# FPGA_Bank_IO.net
KiCad netlist of a schematic drawn in Altium Designer
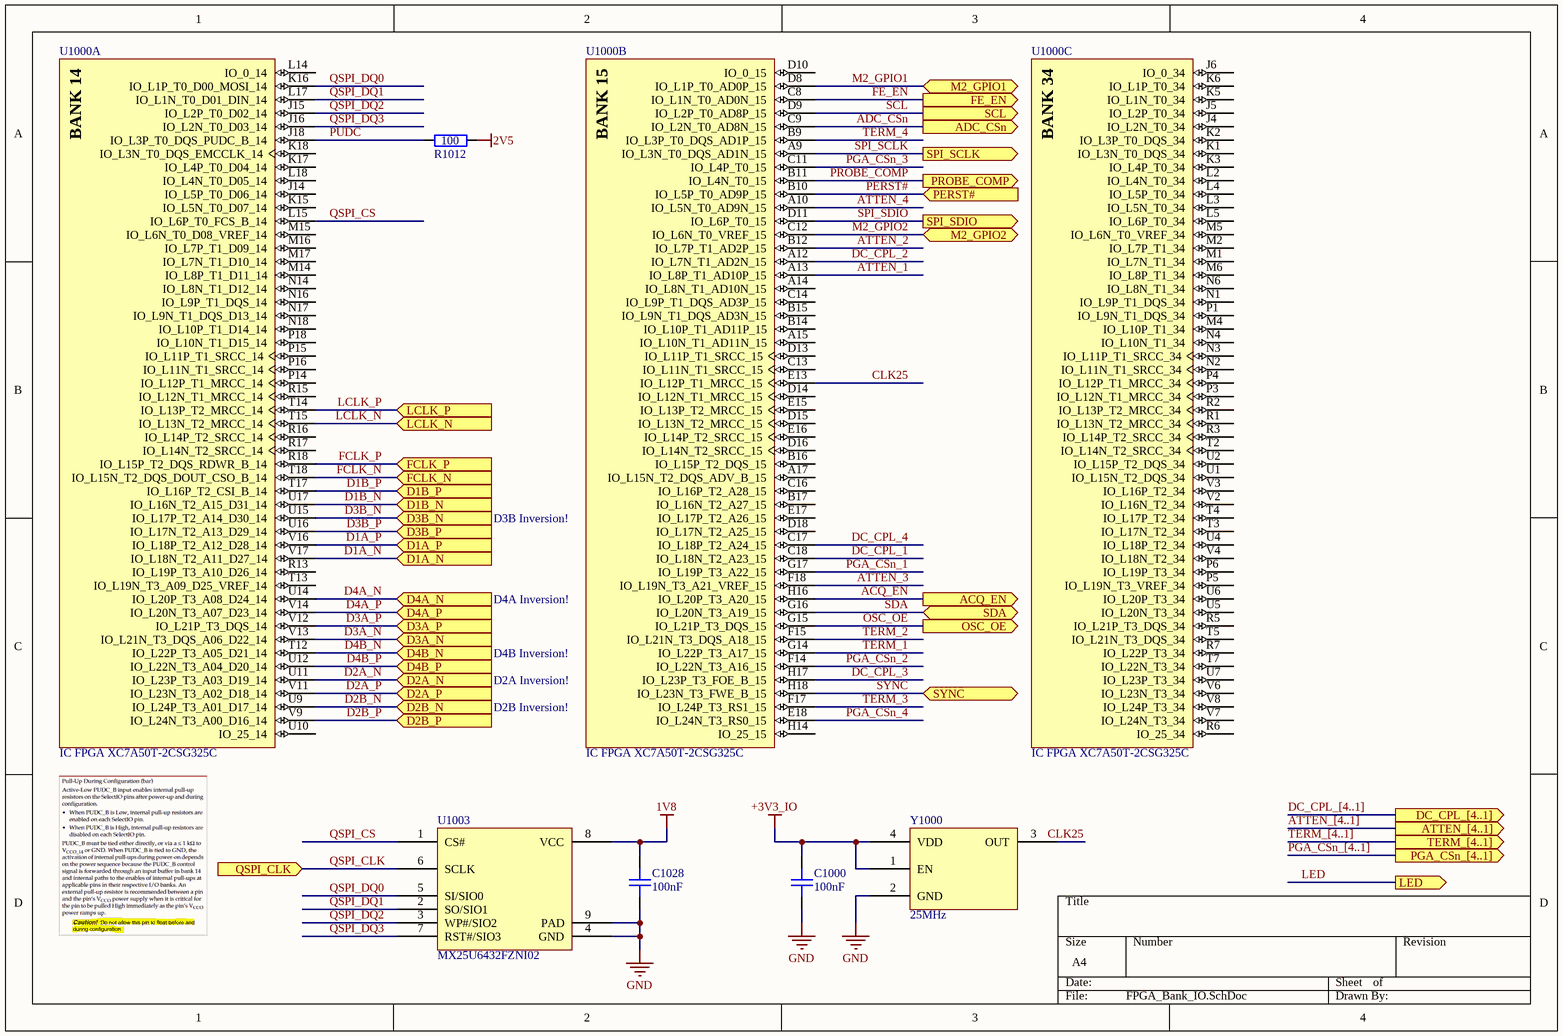
[diagram p0: FPGA_Bank_IO.SchDoc]

(export (version "E")
  (design (tool "Eeschema 10.0.6"))
  (components
    (comp (ref "C1000")
      (value "100nF")
      (footprint "GEN_C_0402")
      (fields
        (field (name "HOUSE PART NUMBER") "C-100nF-0402-002")
        (field (name "MANUFACTURER") "Murata")
        (field (name "MANUFACTURER PART NUMBER") "GCM155R71C104KA55D")
      )
      (libsource (lib "DSO") (part "CAP 100nF 16V X7R 0402"))
    )
    (comp (ref "C1028")
      (value "100nF")
      (footprint "GEN_C_0402")
      (fields
        (field (name "HOUSE PART NUMBER") "C-100nF-0402-002")
        (field (name "MANUFACTURER") "Murata")
        (field (name "MANUFACTURER PART NUMBER") "GCM155R71C104KA55D")
      )
      (libsource (lib "DSO") (part "CAP 100nF 16V X7R 0402"))
    )
    (comp (ref "R1012")
      (value "100")
      (footprint "GEN_R_0402")
      (fields
        (field (name "TOLERANCE") "1%")
        (field (name "MANUFACTURER") "Yageo")
        (field (name "MANUFACTURER PART NUMBER") "RC0402FR-07100RL")
      )
      (libsource (lib "DSO") (part "RES 100 OHM 1% 1/10W 0402"))
    )
    (comp (ref "U1000")
      (value "IC FPGA XC7A50T-2CSG325C")
      (footprint "XILINX_XC7A50T-2CSG325C")
      (description "Artix-7 FPGA, 150 User I/Os, 4 GTP, 324-Ball BGA, Speed Grade 2, Commercial Grade, Pb-Free")
      (fields (field (name "MANUFACTURER") "Xilinx") (field (name "HOUSE PART NUMBER") "XC7A50T-2CSG325C"))
      (libsource (lib "DSO") (part "IC FPGA XC7A50T-2CSG325C"))
    )
    (comp (ref "U1003")
      (value "MX25U6432FZNI02")
      (footprint "MX_WSON8")
      (fields (field (name "MANUFACTURER") "Macronix"))
      (libsource (lib "DSO") (part "IC FLASH MX25U6432FZNI02"))
    )
    (comp (ref "Y1000")
      (value "25MHz")
      (footprint "ECS_TXO-2016")
      (fields
        (field (name "HOUSE PART NUMBER") "ECS-TXO-2016-33-250-TR")
        (field (name "MANUFACTURER") "ECS International")
      )
      (libsource (lib "DSO") (part "OSC 25MHz ECS-TXO-2016"))
    )
  )
  (nets
    (net (code "1") (name "+3V3_IO") (class "Default")
      (node (ref "C1000") (pin "1") (pinfunction "1_1") (pintype "passive"))
      (node (ref "Y1000") (pin "1") (pinfunction "EN_1") (pintype "passive"))
      (node (ref "Y1000") (pin "4") (pinfunction "VDD_4") (pintype "power_in"))
    )
    (net (code "2") (name "/ACQ_EN") (class "Default")
      (node (ref "U1000") (pin "H16") (pinfunction "IO_L20P_T3_A20_15_H16") (pintype "bidirectional"))
    )
    (net (code "3") (name "/ADC_CSn") (class "Default")
      (node (ref "U1000") (pin "C9") (pinfunction "IO_L2N_T0_AD8N_15_C9") (pintype "bidirectional"))
    )
    (net (code "4") (name "/ATTEN_1") (class "Default")
      (node (ref "U1000") (pin "A13") (pinfunction "IO_L8P_T1_AD10P_15_A13") (pintype "bidirectional"))
    )
    (net (code "5") (name "/ATTEN_2") (class "Default")
      (node (ref "U1000") (pin "B12") (pinfunction "IO_L7P_T1_AD2P_15_B12") (pintype "bidirectional"))
    )
    (net (code "6") (name "/ATTEN_3") (class "Default")
      (node (ref "U1000") (pin "F18") (pinfunction "IO_L19N_T3_A21_VREF_15_F18") (pintype "bidirectional"))
    )
    (net (code "7") (name "/ATTEN_4") (class "Default")
      (node (ref "U1000") (pin "A10") (pinfunction "IO_L5N_T0_AD9N_15_A10") (pintype "bidirectional"))
    )
    (net (code "9") (name "/CLK25") (class "Default")
      (node (ref "U1000") (pin "E13") (pinfunction "IO_L12P_T1_MRCC_15_E13") (pintype "bidirectional"))
      (node (ref "Y1000") (pin "3") (pinfunction "OUT_3") (pintype "passive"))
    )
    (net (code "10") (name "/D1A_N") (class "Default")
      (node (ref "U1000") (pin "V17") (pinfunction "IO_L18N_T2_A11_D27_14_V17") (pintype "bidirectional"))
    )
    (net (code "11") (name "/D1A_P") (class "Default")
      (node (ref "U1000") (pin "V16") (pinfunction "IO_L18P_T2_A12_D28_14_V16") (pintype "bidirectional"))
    )
    (net (code "12") (name "/D1B_N") (class "Default")
      (node (ref "U1000") (pin "U17") (pinfunction "IO_L16N_T2_A15_D31_14_U17") (pintype "bidirectional"))
    )
    (net (code "13") (name "/D1B_P") (class "Default")
      (node (ref "U1000") (pin "T17") (pinfunction "IO_L16P_T2_CSI_B_14_T17") (pintype "bidirectional"))
    )
    (net (code "14") (name "/D2A_N") (class "Default")
      (node (ref "U1000") (pin "U11") (pinfunction "IO_L23P_T3_A03_D19_14_U11") (pintype "bidirectional"))
    )
    (net (code "15") (name "/D2A_P") (class "Default")
      (node (ref "U1000") (pin "V11") (pinfunction "IO_L23N_T3_A02_D18_14_V11") (pintype "bidirectional"))
    )
    (net (code "16") (name "/D2B_N") (class "Default")
      (node (ref "U1000") (pin "U9") (pinfunction "IO_L24P_T3_A01_D17_14_U9") (pintype "bidirectional"))
    )
    (net (code "17") (name "/D2B_P") (class "Default")
      (node (ref "U1000") (pin "V9") (pinfunction "IO_L24N_T3_A00_D16_14_V9") (pintype "bidirectional"))
    )
    (net (code "18") (name "/D3A_N") (class "Default")
      (node (ref "U1000") (pin "V13") (pinfunction "IO_L21N_T3_DQS_A06_D22_14_V13") (pintype "bidirectional"))
    )
    (net (code "19") (name "/D3A_P") (class "Default")
      (node (ref "U1000") (pin "V12") (pinfunction "IO_L21P_T3_DQS_14_V12") (pintype "bidirectional"))
    )
    (net (code "20") (name "/D3B_N") (class "Default")
      (node (ref "U1000") (pin "U15") (pinfunction "IO_L17P_T2_A14_D30_14_U15") (pintype "bidirectional"))
    )
    (net (code "21") (name "/D3B_P") (class "Default")
      (node (ref "U1000") (pin "U16") (pinfunction "IO_L17N_T2_A13_D29_14_U16") (pintype "bidirectional"))
    )
    (net (code "22") (name "/D4A_N") (class "Default")
      (node (ref "U1000") (pin "U14") (pinfunction "IO_L20P_T3_A08_D24_14_U14") (pintype "bidirectional"))
    )
    (net (code "23") (name "/D4A_P") (class "Default")
      (node (ref "U1000") (pin "V14") (pinfunction "IO_L20N_T3_A07_D23_14_V14") (pintype "bidirectional"))
    )
    (net (code "24") (name "/D4B_N") (class "Default")
      (node (ref "U1000") (pin "T12") (pinfunction "IO_L22P_T3_A05_D21_14_T12") (pintype "bidirectional"))
    )
    (net (code "25") (name "/D4B_P") (class "Default")
      (node (ref "U1000") (pin "U12") (pinfunction "IO_L22N_T3_A04_D20_14_U12") (pintype "bidirectional"))
    )
    (net (code "26") (name "/DC_CPL_1") (class "Default")
      (node (ref "U1000") (pin "C18") (pinfunction "IO_L18N_T2_A23_15_C18") (pintype "bidirectional"))
    )
    (net (code "27") (name "/DC_CPL_2") (class "Default")
      (node (ref "U1000") (pin "A12") (pinfunction "IO_L7N_T1_AD2N_15_A12") (pintype "bidirectional"))
    )
    (net (code "28") (name "/DC_CPL_3") (class "Default")
      (node (ref "U1000") (pin "H17") (pinfunction "IO_L23P_T3_FOE_B_15_H17") (pintype "bidirectional"))
    )
    (net (code "29") (name "/DC_CPL_4") (class "Default")
      (node (ref "U1000") (pin "C17") (pinfunction "IO_L18P_T2_A24_15_C17") (pintype "bidirectional"))
    )
    (net (code "31") (name "/FCLK_N") (class "Default")
      (node (ref "U1000") (pin "T18") (pinfunction "IO_L15N_T2_DQS_DOUT_CSO_B_14_T18") (pintype "bidirectional"))
    )
    (net (code "32") (name "/FCLK_P") (class "Default")
      (node (ref "U1000") (pin "R18") (pinfunction "IO_L15P_T2_DQS_RDWR_B_14_R18") (pintype "bidirectional"))
    )
    (net (code "33") (name "/FE_EN") (class "Default")
      (node (ref "U1000") (pin "C8") (pinfunction "IO_L1N_T0_AD0N_15_C8") (pintype "bidirectional"))
    )
    (net (code "34") (name "/LCLK_N") (class "Default")
      (node (ref "U1000") (pin "T15") (pinfunction "IO_L13N_T2_MRCC_14_T15") (pintype "bidirectional"))
    )
    (net (code "35") (name "/LCLK_P") (class "Default")
      (node (ref "U1000") (pin "T14") (pinfunction "IO_L13P_T2_MRCC_14_T14") (pintype "bidirectional"))
    )
    (net (code "37") (name "/M2_GPIO1") (class "Default")
      (node (ref "U1000") (pin "D8") (pinfunction "IO_L1P_T0_AD0P_15_D8") (pintype "bidirectional"))
    )
    (net (code "38") (name "/M2_GPIO2") (class "Default")
      (node (ref "U1000") (pin "C12") (pinfunction "IO_L6N_T0_VREF_15_C12") (pintype "bidirectional"))
    )
    (net (code "39") (name "/OSC_OE") (class "Default")
      (node (ref "U1000") (pin "G15") (pinfunction "IO_L21P_T3_DQS_15_G15") (pintype "bidirectional"))
    )
    (net (code "40") (name "/PERST#") (class "Default")
      (node (ref "U1000") (pin "B10") (pinfunction "IO_L5P_T0_AD9P_15_B10") (pintype "bidirectional"))
    )
    (net (code "41") (name "/PGA_CSn_1") (class "Default")
      (node (ref "U1000") (pin "G17") (pinfunction "IO_L19P_T3_A22_15_G17") (pintype "bidirectional"))
    )
    (net (code "42") (name "/PGA_CSn_2") (class "Default")
      (node (ref "U1000") (pin "F14") (pinfunction "IO_L22N_T3_A16_15_F14") (pintype "bidirectional"))
    )
    (net (code "43") (name "/PGA_CSn_3") (class "Default")
      (node (ref "U1000") (pin "C11") (pinfunction "IO_L4P_T0_15_C11") (pintype "bidirectional"))
    )
    (net (code "44") (name "/PGA_CSn_4") (class "Default")
      (node (ref "U1000") (pin "E18") (pinfunction "IO_L24N_T3_RS0_15_E18") (pintype "bidirectional"))
    )
    (net (code "46") (name "/PROBE_COMP") (class "Default")
      (node (ref "U1000") (pin "B11") (pinfunction "IO_L4N_T0_15_B11") (pintype "bidirectional"))
    )
    (net (code "47") (name "/PUDC") (class "Default")
      (node (ref "R1012") (pin "1") (pinfunction "1_1") (pintype "passive"))
      (node (ref "U1000") (pin "J18") (pinfunction "IO_L3P_T0_DQS_PUDC_B_14_J18") (pintype "bidirectional"))
    )
    (net (code "48") (name "/QSPI_CLK") (class "Default")
      (node (ref "U1003") (pin "6") (pinfunction "SCLK_6") (pintype "passive"))
    )
    (net (code "49") (name "/QSPI_CS") (class "Default")
      (node (ref "U1000") (pin "L15") (pinfunction "IO_L6P_T0_FCS_B_14_L15") (pintype "bidirectional"))
      (node (ref "U1003") (pin "1") (pinfunction "CS#_1") (pintype "passive"))
    )
    (net (code "50") (name "/QSPI_DQ0") (class "Default")
      (node (ref "U1000") (pin "K16") (pinfunction "IO_L1P_T0_D00_MOSI_14_K16") (pintype "bidirectional"))
      (node (ref "U1003") (pin "5") (pinfunction "SI/SIO0_5") (pintype "passive"))
    )
    (net (code "51") (name "/QSPI_DQ1") (class "Default")
      (node (ref "U1000") (pin "L17") (pinfunction "IO_L1N_T0_D01_DIN_14_L17") (pintype "bidirectional"))
      (node (ref "U1003") (pin "2") (pinfunction "SO/SIO1_2") (pintype "passive"))
    )
    (net (code "52") (name "/QSPI_DQ2") (class "Default")
      (node (ref "U1000") (pin "J15") (pinfunction "IO_L2P_T0_D02_14_J15") (pintype "bidirectional"))
      (node (ref "U1003") (pin "3") (pinfunction "WP#/SIO2_3") (pintype "passive"))
    )
    (net (code "53") (name "/QSPI_DQ3") (class "Default")
      (node (ref "U1000") (pin "J16") (pinfunction "IO_L2N_T0_D03_14_J16") (pintype "bidirectional"))
      (node (ref "U1003") (pin "7") (pinfunction "RST#/SIO3_7") (pintype "passive"))
    )
    (net (code "54") (name "/SCL") (class "Default")
      (node (ref "U1000") (pin "D9") (pinfunction "IO_L2P_T0_AD8P_15_D9") (pintype "bidirectional"))
    )
    (net (code "55") (name "/SDA") (class "Default")
      (node (ref "U1000") (pin "G16") (pinfunction "IO_L20N_T3_A19_15_G16") (pintype "bidirectional"))
    )
    (net (code "56") (name "/SPI_SCLK") (class "Default")
      (node (ref "U1000") (pin "A9") (pinfunction "IO_L3N_T0_DQS_AD1N_15_A9") (pintype "bidirectional"))
    )
    (net (code "57") (name "/SPI_SDIO") (class "Default")
      (node (ref "U1000") (pin "D11") (pinfunction "IO_L6P_T0_15_D11") (pintype "bidirectional"))
    )
    (net (code "58") (name "/SYNC") (class "Default")
      (node (ref "U1000") (pin "H18") (pinfunction "IO_L23N_T3_FWE_B_15_H18") (pintype "bidirectional"))
    )
    (net (code "59") (name "/TERM_1") (class "Default")
      (node (ref "U1000") (pin "G14") (pinfunction "IO_L22P_T3_A17_15_G14") (pintype "bidirectional"))
    )
    (net (code "60") (name "/TERM_2") (class "Default")
      (node (ref "U1000") (pin "F15") (pinfunction "IO_L21N_T3_DQS_A18_15_F15") (pintype "bidirectional"))
    )
    (net (code "61") (name "/TERM_3") (class "Default")
      (node (ref "U1000") (pin "F17") (pinfunction "IO_L24P_T3_RS1_15_F17") (pintype "bidirectional"))
    )
    (net (code "62") (name "/TERM_4") (class "Default")
      (node (ref "U1000") (pin "B9") (pinfunction "IO_L3P_T0_DQS_AD1P_15_B9") (pintype "bidirectional"))
    )
    (net (code "64") (name "1V8") (class "Default")
      (node (ref "C1028") (pin "1") (pinfunction "1_1") (pintype "passive"))
      (node (ref "U1003") (pin "8") (pinfunction "VCC_8") (pintype "passive"))
    )
    (net (code "65") (name "2V5") (class "Default")
      (node (ref "R1012") (pin "2") (pinfunction "2_2") (pintype "passive"))
    )
    (net (code "66") (name "GND") (class "Default")
      (node (ref "C1000") (pin "2") (pinfunction "2_2") (pintype "passive"))
      (node (ref "C1028") (pin "2") (pinfunction "2_2") (pintype "passive"))
      (node (ref "U1003") (pin "4") (pinfunction "GND_4") (pintype "passive"))
      (node (ref "U1003") (pin "9") (pinfunction "PAD_9") (pintype "passive"))
      (node (ref "Y1000") (pin "2") (pinfunction "GND_2") (pintype "power_in"))
    )
    (net (code "67") (name "unconnected-(U1000A-IO_0_14-PadL14)") (class "Default")
      (node (ref "U1000") (pin "L14") (pinfunction "IO_0_14_L14") (pintype "bidirectional"))
    )
    (net (code "68") (name "unconnected-(U1000A-IO_25_14-PadU10)") (class "Default")
      (node (ref "U1000") (pin "U10") (pinfunction "IO_25_14_U10") (pintype "bidirectional"))
    )
    (net (code "69") (name "unconnected-(U1000A-IO_L3N_T0_DQS_EMCCLK_14-PadK18)") (class "Default")
      (node (ref "U1000") (pin "K18") (pinfunction "IO_L3N_T0_DQS_EMCCLK_14_K18") (pintype "bidirectional"))
    )
    (net (code "70") (name "unconnected-(U1000A-IO_L4N_T0_D05_14-PadL18)") (class "Default")
      (node (ref "U1000") (pin "L18") (pinfunction "IO_L4N_T0_D05_14_L18") (pintype "bidirectional"))
    )
    (net (code "71") (name "unconnected-(U1000A-IO_L4P_T0_D04_14-PadK17)") (class "Default")
      (node (ref "U1000") (pin "K17") (pinfunction "IO_L4P_T0_D04_14_K17") (pintype "bidirectional"))
    )
    (net (code "72") (name "unconnected-(U1000A-IO_L5N_T0_D07_14-PadK15)") (class "Default")
      (node (ref "U1000") (pin "K15") (pinfunction "IO_L5N_T0_D07_14_K15") (pintype "bidirectional"))
    )
    (net (code "73") (name "unconnected-(U1000A-IO_L5P_T0_D06_14-PadJ14)") (class "Default")
      (node (ref "U1000") (pin "J14") (pinfunction "IO_L5P_T0_D06_14_J14") (pintype "bidirectional"))
    )
    (net (code "74") (name "unconnected-(U1000A-IO_L6N_T0_D08_VREF_14-PadM15)") (class "Default")
      (node (ref "U1000") (pin "M15") (pinfunction "IO_L6N_T0_D08_VREF_14_M15") (pintype "bidirectional"))
    )
    (net (code "75") (name "unconnected-(U1000A-IO_L7N_T1_D10_14-PadM17)") (class "Default")
      (node (ref "U1000") (pin "M17") (pinfunction "IO_L7N_T1_D10_14_M17") (pintype "bidirectional"))
    )
    (net (code "76") (name "unconnected-(U1000A-IO_L7P_T1_D09_14-PadM16)") (class "Default")
      (node (ref "U1000") (pin "M16") (pinfunction "IO_L7P_T1_D09_14_M16") (pintype "bidirectional"))
    )
    (net (code "77") (name "unconnected-(U1000A-IO_L8N_T1_D12_14-PadN14)") (class "Default")
      (node (ref "U1000") (pin "N14") (pinfunction "IO_L8N_T1_D12_14_N14") (pintype "bidirectional"))
    )
    (net (code "78") (name "unconnected-(U1000A-IO_L8P_T1_D11_14-PadM14)") (class "Default")
      (node (ref "U1000") (pin "M14") (pinfunction "IO_L8P_T1_D11_14_M14") (pintype "bidirectional"))
    )
    (net (code "79") (name "unconnected-(U1000A-IO_L9N_T1_DQS_D13_14-PadN17)") (class "Default")
      (node (ref "U1000") (pin "N17") (pinfunction "IO_L9N_T1_DQS_D13_14_N17") (pintype "bidirectional"))
    )
    (net (code "80") (name "unconnected-(U1000A-IO_L9P_T1_DQS_14-PadN16)") (class "Default")
      (node (ref "U1000") (pin "N16") (pinfunction "IO_L9P_T1_DQS_14_N16") (pintype "bidirectional"))
    )
    (net (code "81") (name "unconnected-(U1000A-IO_L10N_T1_D15_14-PadP18)") (class "Default")
      (node (ref "U1000") (pin "P18") (pinfunction "IO_L10N_T1_D15_14_P18") (pintype "bidirectional"))
    )
    (net (code "82") (name "unconnected-(U1000A-IO_L10P_T1_D14_14-PadN18)") (class "Default")
      (node (ref "U1000") (pin "N18") (pinfunction "IO_L10P_T1_D14_14_N18") (pintype "bidirectional"))
    )
    (net (code "83") (name "unconnected-(U1000A-IO_L11N_T1_SRCC_14-PadP16)") (class "Default")
      (node (ref "U1000") (pin "P16") (pinfunction "IO_L11N_T1_SRCC_14_P16") (pintype "bidirectional"))
    )
    (net (code "84") (name "unconnected-(U1000A-IO_L11P_T1_SRCC_14-PadP15)") (class "Default")
      (node (ref "U1000") (pin "P15") (pinfunction "IO_L11P_T1_SRCC_14_P15") (pintype "bidirectional"))
    )
    (net (code "85") (name "unconnected-(U1000A-IO_L12N_T1_MRCC_14-PadR15)") (class "Default")
      (node (ref "U1000") (pin "R15") (pinfunction "IO_L12N_T1_MRCC_14_R15") (pintype "bidirectional"))
    )
    (net (code "86") (name "unconnected-(U1000A-IO_L12P_T1_MRCC_14-PadP14)") (class "Default")
      (node (ref "U1000") (pin "P14") (pinfunction "IO_L12P_T1_MRCC_14_P14") (pintype "bidirectional"))
    )
    (net (code "87") (name "unconnected-(U1000A-IO_L14N_T2_SRCC_14-PadR17)") (class "Default")
      (node (ref "U1000") (pin "R17") (pinfunction "IO_L14N_T2_SRCC_14_R17") (pintype "bidirectional"))
    )
    (net (code "88") (name "unconnected-(U1000A-IO_L14P_T2_SRCC_14-PadR16)") (class "Default")
      (node (ref "U1000") (pin "R16") (pinfunction "IO_L14P_T2_SRCC_14_R16") (pintype "bidirectional"))
    )
    (net (code "89") (name "unconnected-(U1000A-IO_L19N_T3_A09_D25_VREF_14-PadT13)") (class "Default")
      (node (ref "U1000") (pin "T13") (pinfunction "IO_L19N_T3_A09_D25_VREF_14_T13") (pintype "bidirectional"))
    )
    (net (code "90") (name "unconnected-(U1000A-IO_L19P_T3_A10_D26_14-PadR13)") (class "Default")
      (node (ref "U1000") (pin "R13") (pinfunction "IO_L19P_T3_A10_D26_14_R13") (pintype "bidirectional"))
    )
    (net (code "91") (name "unconnected-(U1000B-IO_0_15-PadD10)") (class "Default")
      (node (ref "U1000") (pin "D10") (pinfunction "IO_0_15_D10") (pintype "bidirectional"))
    )
    (net (code "92") (name "unconnected-(U1000B-IO_25_15-PadH14)") (class "Default")
      (node (ref "U1000") (pin "H14") (pinfunction "IO_25_15_H14") (pintype "bidirectional"))
    )
    (net (code "93") (name "unconnected-(U1000B-IO_L8N_T1_AD10N_15-PadA14)") (class "Default")
      (node (ref "U1000") (pin "A14") (pinfunction "IO_L8N_T1_AD10N_15_A14") (pintype "bidirectional"))
    )
    (net (code "94") (name "unconnected-(U1000B-IO_L9N_T1_DQS_AD3N_15-PadB15)") (class "Default")
      (node (ref "U1000") (pin "B15") (pinfunction "IO_L9N_T1_DQS_AD3N_15_B15") (pintype "bidirectional"))
    )
    (net (code "95") (name "unconnected-(U1000B-IO_L9P_T1_DQS_AD3P_15-PadC14)") (class "Default")
      (node (ref "U1000") (pin "C14") (pinfunction "IO_L9P_T1_DQS_AD3P_15_C14") (pintype "bidirectional"))
    )
    (net (code "96") (name "unconnected-(U1000B-IO_L10N_T1_AD11N_15-PadA15)") (class "Default")
      (node (ref "U1000") (pin "A15") (pinfunction "IO_L10N_T1_AD11N_15_A15") (pintype "bidirectional"))
    )
    (net (code "97") (name "unconnected-(U1000B-IO_L10P_T1_AD11P_15-PadB14)") (class "Default")
      (node (ref "U1000") (pin "B14") (pinfunction "IO_L10P_T1_AD11P_15_B14") (pintype "bidirectional"))
    )
    (net (code "98") (name "unconnected-(U1000B-IO_L11N_T1_SRCC_15-PadC13)") (class "Default")
      (node (ref "U1000") (pin "C13") (pinfunction "IO_L11N_T1_SRCC_15_C13") (pintype "bidirectional"))
    )
    (net (code "99") (name "unconnected-(U1000B-IO_L11P_T1_SRCC_15-PadD13)") (class "Default")
      (node (ref "U1000") (pin "D13") (pinfunction "IO_L11P_T1_SRCC_15_D13") (pintype "bidirectional"))
    )
    (net (code "100") (name "unconnected-(U1000B-IO_L12N_T1_MRCC_15-PadD14)") (class "Default")
      (node (ref "U1000") (pin "D14") (pinfunction "IO_L12N_T1_MRCC_15_D14") (pintype "bidirectional"))
    )
    (net (code "101") (name "unconnected-(U1000B-IO_L13N_T2_MRCC_15-PadD15)") (class "Default")
      (node (ref "U1000") (pin "D15") (pinfunction "IO_L13N_T2_MRCC_15_D15") (pintype "bidirectional"))
    )
    (net (code "102") (name "unconnected-(U1000B-IO_L13P_T2_MRCC_15-PadE15)") (class "Default")
      (node (ref "U1000") (pin "E15") (pinfunction "IO_L13P_T2_MRCC_15_E15") (pintype "bidirectional"))
    )
    (net (code "103") (name "unconnected-(U1000B-IO_L14N_T2_SRCC_15-PadD16)") (class "Default")
      (node (ref "U1000") (pin "D16") (pinfunction "IO_L14N_T2_SRCC_15_D16") (pintype "bidirectional"))
    )
    (net (code "104") (name "unconnected-(U1000B-IO_L14P_T2_SRCC_15-PadE16)") (class "Default")
      (node (ref "U1000") (pin "E16") (pinfunction "IO_L14P_T2_SRCC_15_E16") (pintype "bidirectional"))
    )
    (net (code "105") (name "unconnected-(U1000B-IO_L15N_T2_DQS_ADV_B_15-PadA17)") (class "Default")
      (node (ref "U1000") (pin "A17") (pinfunction "IO_L15N_T2_DQS_ADV_B_15_A17") (pintype "bidirectional"))
    )
    (net (code "106") (name "unconnected-(U1000B-IO_L15P_T2_DQS_15-PadB16)") (class "Default")
      (node (ref "U1000") (pin "B16") (pinfunction "IO_L15P_T2_DQS_15_B16") (pintype "bidirectional"))
    )
    (net (code "107") (name "unconnected-(U1000B-IO_L16N_T2_A27_15-PadB17)") (class "Default")
      (node (ref "U1000") (pin "B17") (pinfunction "IO_L16N_T2_A27_15_B17") (pintype "bidirectional"))
    )
    (net (code "108") (name "unconnected-(U1000B-IO_L16P_T2_A28_15-PadC16)") (class "Default")
      (node (ref "U1000") (pin "C16") (pinfunction "IO_L16P_T2_A28_15_C16") (pintype "bidirectional"))
    )
    (net (code "109") (name "unconnected-(U1000B-IO_L17N_T2_A25_15-PadD18)") (class "Default")
      (node (ref "U1000") (pin "D18") (pinfunction "IO_L17N_T2_A25_15_D18") (pintype "bidirectional"))
    )
    (net (code "110") (name "unconnected-(U1000B-IO_L17P_T2_A26_15-PadE17)") (class "Default")
      (node (ref "U1000") (pin "E17") (pinfunction "IO_L17P_T2_A26_15_E17") (pintype "bidirectional"))
    )
    (net (code "111") (name "unconnected-(U1000C-IO_0_34-PadJ6)") (class "Default")
      (node (ref "U1000") (pin "J6") (pinfunction "IO_0_34_J6") (pintype "bidirectional"))
    )
    (net (code "112") (name "unconnected-(U1000C-IO_25_34-PadR6)") (class "Default")
      (node (ref "U1000") (pin "R6") (pinfunction "IO_25_34_R6") (pintype "bidirectional"))
    )
    (net (code "113") (name "unconnected-(U1000C-IO_L1N_T0_34-PadK5)") (class "Default")
      (node (ref "U1000") (pin "K5") (pinfunction "IO_L1N_T0_34_K5") (pintype "bidirectional"))
    )
    (net (code "114") (name "unconnected-(U1000C-IO_L1P_T0_34-PadK6)") (class "Default")
      (node (ref "U1000") (pin "K6") (pinfunction "IO_L1P_T0_34_K6") (pintype "bidirectional"))
    )
    (net (code "115") (name "unconnected-(U1000C-IO_L2N_T0_34-PadJ4)") (class "Default")
      (node (ref "U1000") (pin "J4") (pinfunction "IO_L2N_T0_34_J4") (pintype "bidirectional"))
    )
    (net (code "116") (name "unconnected-(U1000C-IO_L2P_T0_34-PadJ5)") (class "Default")
      (node (ref "U1000") (pin "J5") (pinfunction "IO_L2P_T0_34_J5") (pintype "bidirectional"))
    )
    (net (code "117") (name "unconnected-(U1000C-IO_L3N_T0_DQS_34-PadK1)") (class "Default")
      (node (ref "U1000") (pin "K1") (pinfunction "IO_L3N_T0_DQS_34_K1") (pintype "bidirectional"))
    )
    (net (code "118") (name "unconnected-(U1000C-IO_L3P_T0_DQS_34-PadK2)") (class "Default")
      (node (ref "U1000") (pin "K2") (pinfunction "IO_L3P_T0_DQS_34_K2") (pintype "bidirectional"))
    )
    (net (code "119") (name "unconnected-(U1000C-IO_L4N_T0_34-PadL2)") (class "Default")
      (node (ref "U1000") (pin "L2") (pinfunction "IO_L4N_T0_34_L2") (pintype "bidirectional"))
    )
    (net (code "120") (name "unconnected-(U1000C-IO_L4P_T0_34-PadK3)") (class "Default")
      (node (ref "U1000") (pin "K3") (pinfunction "IO_L4P_T0_34_K3") (pintype "bidirectional"))
    )
    (net (code "121") (name "unconnected-(U1000C-IO_L5N_T0_34-PadL3)") (class "Default")
      (node (ref "U1000") (pin "L3") (pinfunction "IO_L5N_T0_34_L3") (pintype "bidirectional"))
    )
    (net (code "122") (name "unconnected-(U1000C-IO_L5P_T0_34-PadL4)") (class "Default")
      (node (ref "U1000") (pin "L4") (pinfunction "IO_L5P_T0_34_L4") (pintype "bidirectional"))
    )
    (net (code "123") (name "unconnected-(U1000C-IO_L6N_T0_VREF_34-PadM5)") (class "Default")
      (node (ref "U1000") (pin "M5") (pinfunction "IO_L6N_T0_VREF_34_M5") (pintype "bidirectional"))
    )
    (net (code "124") (name "unconnected-(U1000C-IO_L6P_T0_34-PadL5)") (class "Default")
      (node (ref "U1000") (pin "L5") (pinfunction "IO_L6P_T0_34_L5") (pintype "bidirectional"))
    )
    (net (code "125") (name "unconnected-(U1000C-IO_L7N_T1_34-PadM1)") (class "Default")
      (node (ref "U1000") (pin "M1") (pinfunction "IO_L7N_T1_34_M1") (pintype "bidirectional"))
    )
    (net (code "126") (name "unconnected-(U1000C-IO_L7P_T1_34-PadM2)") (class "Default")
      (node (ref "U1000") (pin "M2") (pinfunction "IO_L7P_T1_34_M2") (pintype "bidirectional"))
    )
    (net (code "127") (name "unconnected-(U1000C-IO_L8N_T1_34-PadN6)") (class "Default")
      (node (ref "U1000") (pin "N6") (pinfunction "IO_L8N_T1_34_N6") (pintype "bidirectional"))
    )
    (net (code "128") (name "unconnected-(U1000C-IO_L8P_T1_34-PadM6)") (class "Default")
      (node (ref "U1000") (pin "M6") (pinfunction "IO_L8P_T1_34_M6") (pintype "bidirectional"))
    )
    (net (code "129") (name "unconnected-(U1000C-IO_L9N_T1_DQS_34-PadP1)") (class "Default")
      (node (ref "U1000") (pin "P1") (pinfunction "IO_L9N_T1_DQS_34_P1") (pintype "bidirectional"))
    )
    (net (code "130") (name "unconnected-(U1000C-IO_L9P_T1_DQS_34-PadN1)") (class "Default")
      (node (ref "U1000") (pin "N1") (pinfunction "IO_L9P_T1_DQS_34_N1") (pintype "bidirectional"))
    )
    (net (code "131") (name "unconnected-(U1000C-IO_L10N_T1_34-PadN4)") (class "Default")
      (node (ref "U1000") (pin "N4") (pinfunction "IO_L10N_T1_34_N4") (pintype "bidirectional"))
    )
    (net (code "132") (name "unconnected-(U1000C-IO_L10P_T1_34-PadM4)") (class "Default")
      (node (ref "U1000") (pin "M4") (pinfunction "IO_L10P_T1_34_M4") (pintype "bidirectional"))
    )
    (net (code "133") (name "unconnected-(U1000C-IO_L11N_T1_SRCC_34-PadN2)") (class "Default")
      (node (ref "U1000") (pin "N2") (pinfunction "IO_L11N_T1_SRCC_34_N2") (pintype "bidirectional"))
    )
    (net (code "134") (name "unconnected-(U1000C-IO_L11P_T1_SRCC_34-PadN3)") (class "Default")
      (node (ref "U1000") (pin "N3") (pinfunction "IO_L11P_T1_SRCC_34_N3") (pintype "bidirectional"))
    )
    (net (code "135") (name "unconnected-(U1000C-IO_L12N_T1_MRCC_34-PadP3)") (class "Default")
      (node (ref "U1000") (pin "P3") (pinfunction "IO_L12N_T1_MRCC_34_P3") (pintype "bidirectional"))
    )
    (net (code "136") (name "unconnected-(U1000C-IO_L12P_T1_MRCC_34-PadP4)") (class "Default")
      (node (ref "U1000") (pin "P4") (pinfunction "IO_L12P_T1_MRCC_34_P4") (pintype "bidirectional"))
    )
    (net (code "137") (name "unconnected-(U1000C-IO_L13N_T2_MRCC_34-PadR1)") (class "Default")
      (node (ref "U1000") (pin "R1") (pinfunction "IO_L13N_T2_MRCC_34_R1") (pintype "bidirectional"))
    )
    (net (code "138") (name "unconnected-(U1000C-IO_L13P_T2_MRCC_34-PadR2)") (class "Default")
      (node (ref "U1000") (pin "R2") (pinfunction "IO_L13P_T2_MRCC_34_R2") (pintype "bidirectional"))
    )
    (net (code "139") (name "unconnected-(U1000C-IO_L14N_T2_SRCC_34-PadT2)") (class "Default")
      (node (ref "U1000") (pin "T2") (pinfunction "IO_L14N_T2_SRCC_34_T2") (pintype "bidirectional"))
    )
    (net (code "140") (name "unconnected-(U1000C-IO_L14P_T2_SRCC_34-PadR3)") (class "Default")
      (node (ref "U1000") (pin "R3") (pinfunction "IO_L14P_T2_SRCC_34_R3") (pintype "bidirectional"))
    )
    (net (code "141") (name "unconnected-(U1000C-IO_L15N_T2_DQS_34-PadU1)") (class "Default")
      (node (ref "U1000") (pin "U1") (pinfunction "IO_L15N_T2_DQS_34_U1") (pintype "bidirectional"))
    )
    (net (code "142") (name "unconnected-(U1000C-IO_L15P_T2_DQS_34-PadU2)") (class "Default")
      (node (ref "U1000") (pin "U2") (pinfunction "IO_L15P_T2_DQS_34_U2") (pintype "bidirectional"))
    )
    (net (code "143") (name "unconnected-(U1000C-IO_L16N_T2_34-PadV2)") (class "Default")
      (node (ref "U1000") (pin "V2") (pinfunction "IO_L16N_T2_34_V2") (pintype "bidirectional"))
    )
    (net (code "144") (name "unconnected-(U1000C-IO_L16P_T2_34-PadV3)") (class "Default")
      (node (ref "U1000") (pin "V3") (pinfunction "IO_L16P_T2_34_V3") (pintype "bidirectional"))
    )
    (net (code "145") (name "unconnected-(U1000C-IO_L17N_T2_34-PadT3)") (class "Default")
      (node (ref "U1000") (pin "T3") (pinfunction "IO_L17N_T2_34_T3") (pintype "bidirectional"))
    )
    (net (code "146") (name "unconnected-(U1000C-IO_L17P_T2_34-PadT4)") (class "Default")
      (node (ref "U1000") (pin "T4") (pinfunction "IO_L17P_T2_34_T4") (pintype "bidirectional"))
    )
    (net (code "147") (name "unconnected-(U1000C-IO_L18N_T2_34-PadV4)") (class "Default")
      (node (ref "U1000") (pin "V4") (pinfunction "IO_L18N_T2_34_V4") (pintype "bidirectional"))
    )
    (net (code "148") (name "unconnected-(U1000C-IO_L18P_T2_34-PadU4)") (class "Default")
      (node (ref "U1000") (pin "U4") (pinfunction "IO_L18P_T2_34_U4") (pintype "bidirectional"))
    )
    (net (code "149") (name "unconnected-(U1000C-IO_L19N_T3_VREF_34-PadP5)") (class "Default")
      (node (ref "U1000") (pin "P5") (pinfunction "IO_L19N_T3_VREF_34_P5") (pintype "bidirectional"))
    )
    (net (code "150") (name "unconnected-(U1000C-IO_L19P_T3_34-PadP6)") (class "Default")
      (node (ref "U1000") (pin "P6") (pinfunction "IO_L19P_T3_34_P6") (pintype "bidirectional"))
    )
    (net (code "151") (name "unconnected-(U1000C-IO_L20N_T3_34-PadU5)") (class "Default")
      (node (ref "U1000") (pin "U5") (pinfunction "IO_L20N_T3_34_U5") (pintype "bidirectional"))
    )
    (net (code "152") (name "unconnected-(U1000C-IO_L20P_T3_34-PadU6)") (class "Default")
      (node (ref "U1000") (pin "U6") (pinfunction "IO_L20P_T3_34_U6") (pintype "bidirectional"))
    )
    (net (code "153") (name "unconnected-(U1000C-IO_L21N_T3_DQS_34-PadT5)") (class "Default")
      (node (ref "U1000") (pin "T5") (pinfunction "IO_L21N_T3_DQS_34_T5") (pintype "bidirectional"))
    )
    (net (code "154") (name "unconnected-(U1000C-IO_L21P_T3_DQS_34-PadR5)") (class "Default")
      (node (ref "U1000") (pin "R5") (pinfunction "IO_L21P_T3_DQS_34_R5") (pintype "bidirectional"))
    )
    (net (code "155") (name "unconnected-(U1000C-IO_L22N_T3_34-PadT7)") (class "Default")
      (node (ref "U1000") (pin "T7") (pinfunction "IO_L22N_T3_34_T7") (pintype "bidirectional"))
    )
    (net (code "156") (name "unconnected-(U1000C-IO_L22P_T3_34-PadR7)") (class "Default")
      (node (ref "U1000") (pin "R7") (pinfunction "IO_L22P_T3_34_R7") (pintype "bidirectional"))
    )
    (net (code "157") (name "unconnected-(U1000C-IO_L23N_T3_34-PadV6)") (class "Default")
      (node (ref "U1000") (pin "V6") (pinfunction "IO_L23N_T3_34_V6") (pintype "bidirectional"))
    )
    (net (code "158") (name "unconnected-(U1000C-IO_L23P_T3_34-PadU7)") (class "Default")
      (node (ref "U1000") (pin "U7") (pinfunction "IO_L23P_T3_34_U7") (pintype "bidirectional"))
    )
    (net (code "159") (name "unconnected-(U1000C-IO_L24N_T3_34-PadV7)") (class "Default")
      (node (ref "U1000") (pin "V7") (pinfunction "IO_L24N_T3_34_V7") (pintype "bidirectional"))
    )
    (net (code "160") (name "unconnected-(U1000C-IO_L24P_T3_34-PadV8)") (class "Default")
      (node (ref "U1000") (pin "V8") (pinfunction "IO_L24P_T3_34_V8") (pintype "bidirectional"))
    )
  )
)
